# BIT_4.net
KiCad netlist of a schematic drawn in EasyEDA
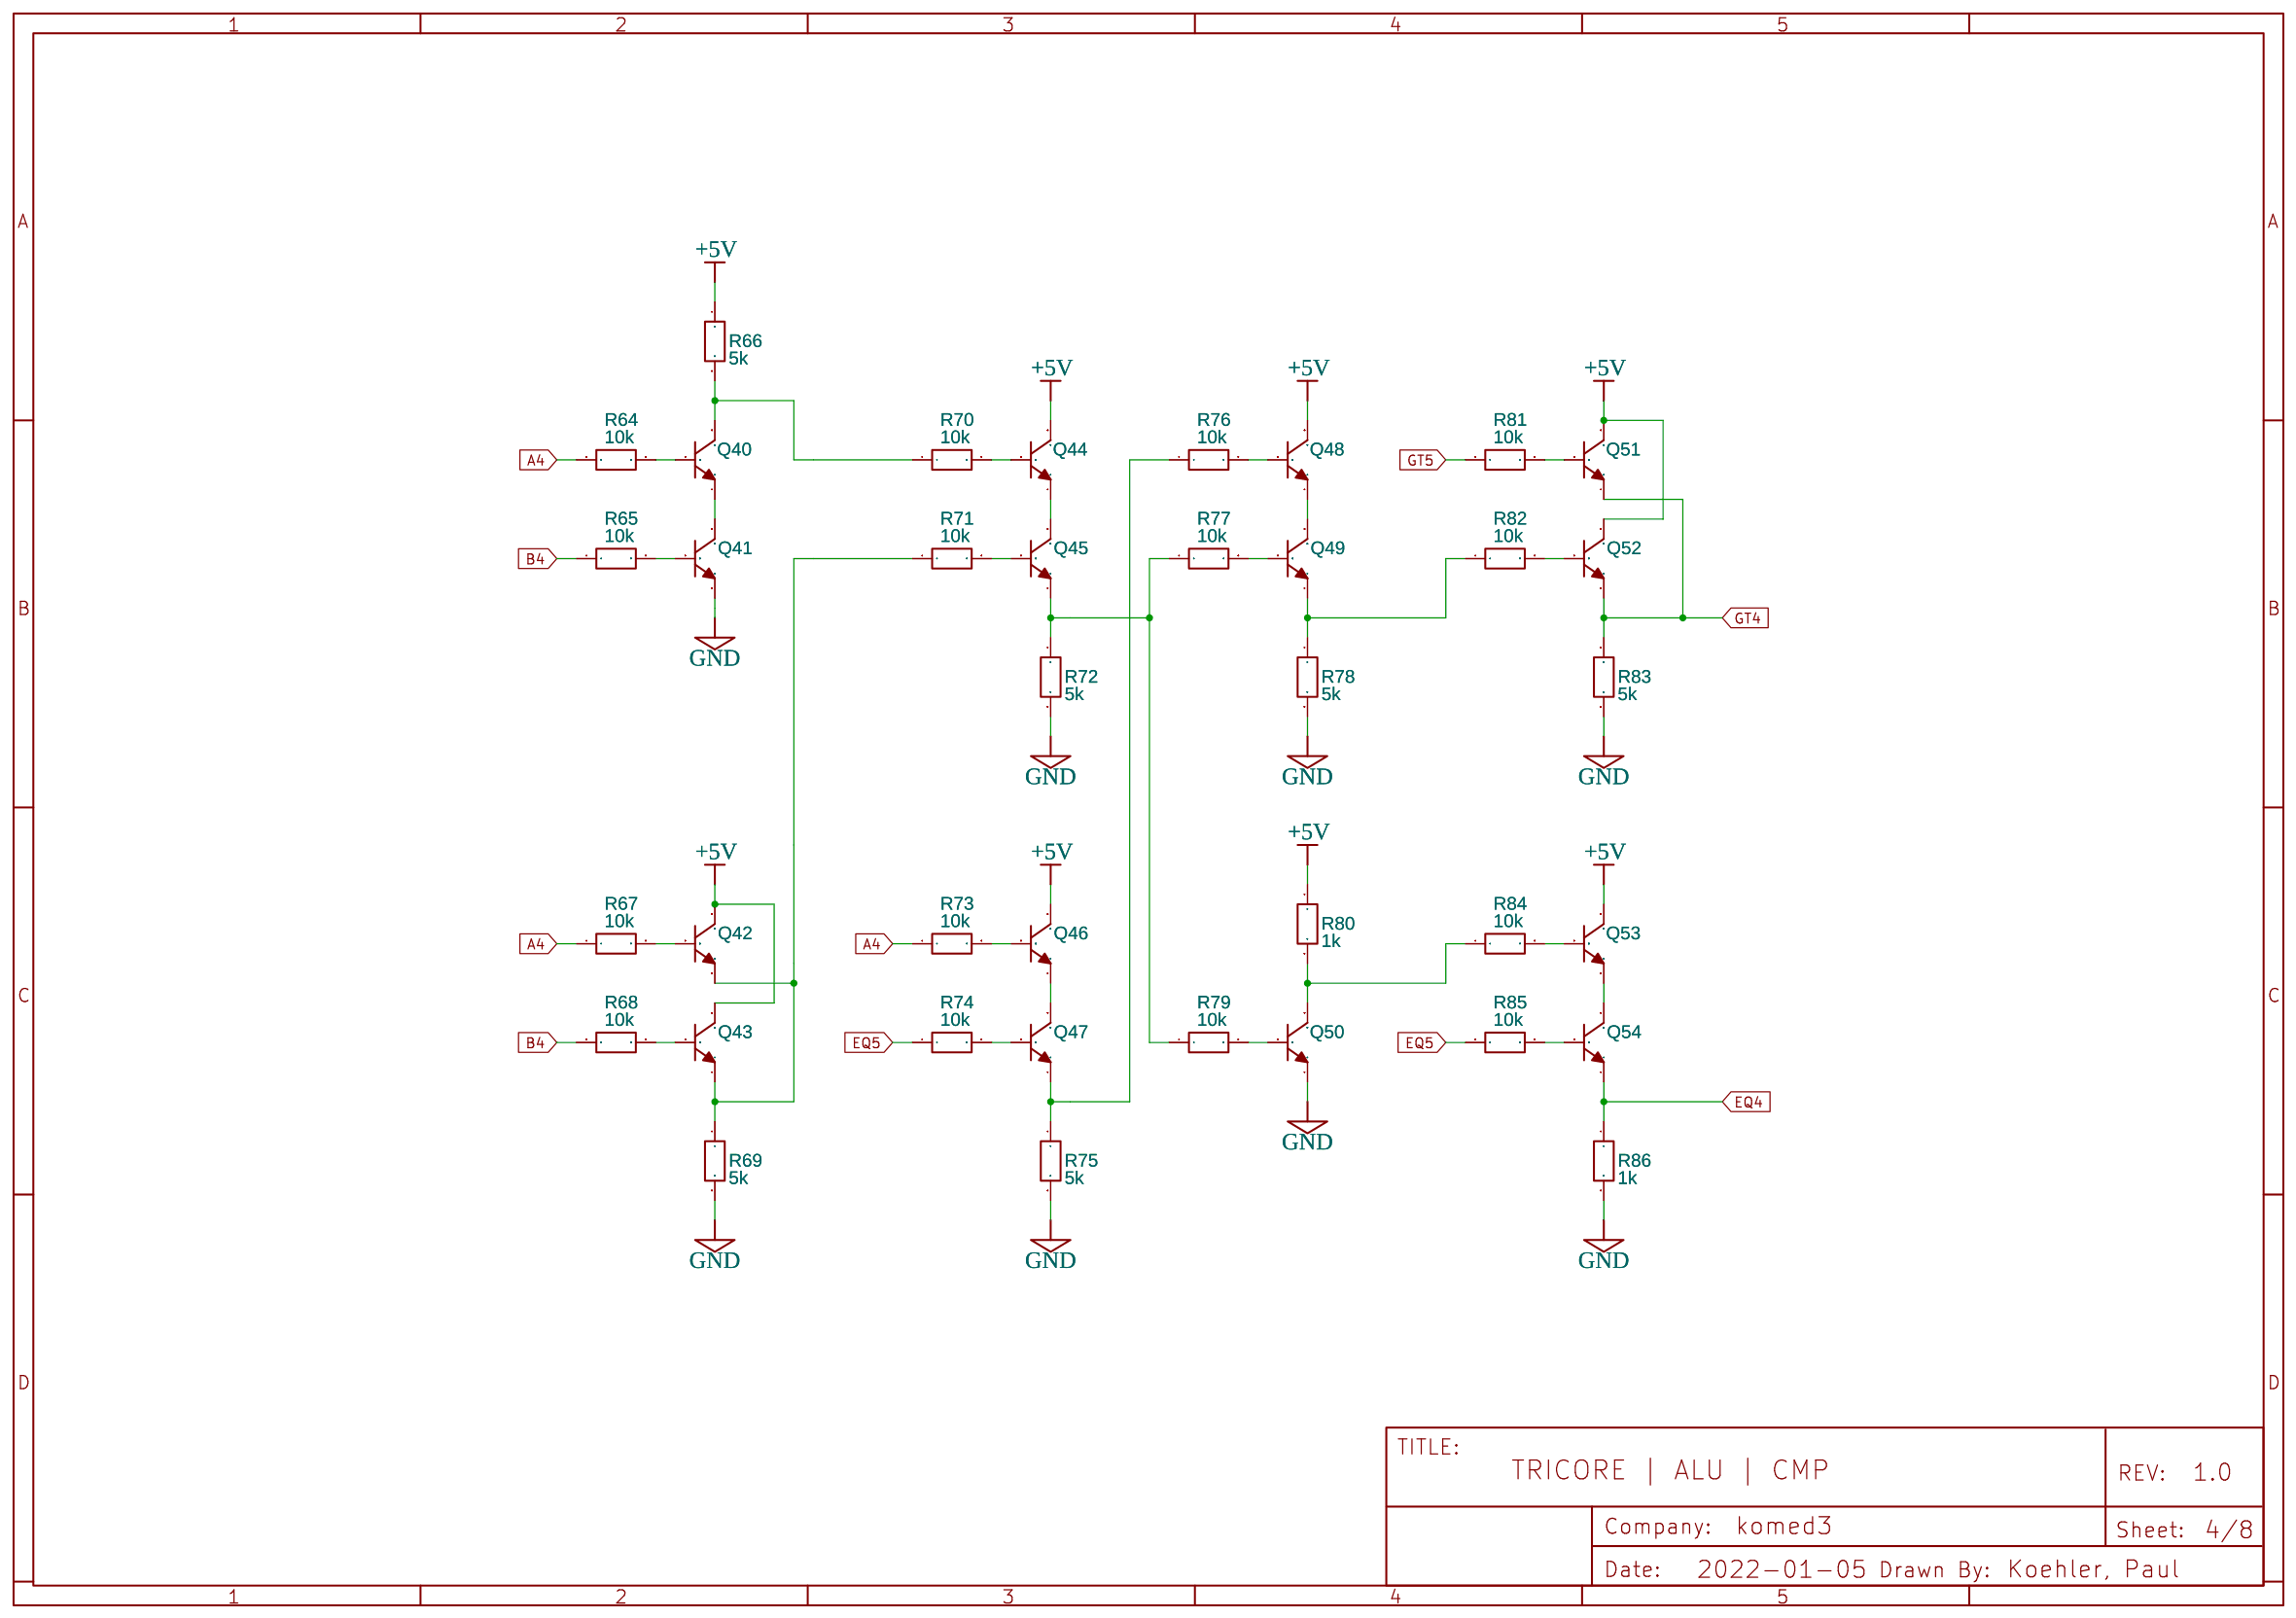
[diagram p0: schematic sheet]

(export (version "E")
  (design (tool "Eeschema 10.0.6"))
  (components
    (comp (ref "Q40")
      (value "2N3904(TO-92)")
      (fields (field (name "BOM_Manufacturer Part") "2N3904") (field (name "BOM_Supplier Part") "C118538"))
      (libsource (lib "") (part "2N3904(TO-92)"))
    )
    (comp (ref "Q41")
      (value "2N3904(TO-92)")
      (fields (field (name "BOM_Manufacturer Part") "2N3904") (field (name "BOM_Supplier Part") "C118538"))
      (libsource (lib "") (part "2N3904(TO-92)"))
    )
    (comp (ref "Q42")
      (value "2N3904(TO-92)")
      (fields (field (name "BOM_Manufacturer Part") "2N3904") (field (name "BOM_Supplier Part") "C118538"))
      (libsource (lib "") (part "2N3904(TO-92)"))
    )
    (comp (ref "Q43")
      (value "2N3904(TO-92)")
      (fields (field (name "BOM_Manufacturer Part") "2N3904") (field (name "BOM_Supplier Part") "C118538"))
      (libsource (lib "") (part "2N3904(TO-92)"))
    )
    (comp (ref "Q44")
      (value "2N3904(TO-92)")
      (fields (field (name "BOM_Manufacturer Part") "2N3904") (field (name "BOM_Supplier Part") "C118538"))
      (libsource (lib "") (part "2N3904(TO-92)"))
    )
    (comp (ref "Q45")
      (value "2N3904(TO-92)")
      (fields (field (name "BOM_Manufacturer Part") "2N3904") (field (name "BOM_Supplier Part") "C118538"))
      (libsource (lib "") (part "2N3904(TO-92)"))
    )
    (comp (ref "Q46")
      (value "2N3904(TO-92)")
      (fields (field (name "BOM_Manufacturer Part") "2N3904") (field (name "BOM_Supplier Part") "C118538"))
      (libsource (lib "") (part "2N3904(TO-92)"))
    )
    (comp (ref "Q47")
      (value "2N3904(TO-92)")
      (fields (field (name "BOM_Manufacturer Part") "2N3904") (field (name "BOM_Supplier Part") "C118538"))
      (libsource (lib "") (part "2N3904(TO-92)"))
    )
    (comp (ref "Q48")
      (value "2N3904(TO-92)")
      (fields (field (name "BOM_Manufacturer Part") "2N3904") (field (name "BOM_Supplier Part") "C118538"))
      (libsource (lib "") (part "2N3904(TO-92)"))
    )
    (comp (ref "Q49")
      (value "2N3904(TO-92)")
      (fields (field (name "BOM_Manufacturer Part") "2N3904") (field (name "BOM_Supplier Part") "C118538"))
      (libsource (lib "") (part "2N3904(TO-92)"))
    )
    (comp (ref "Q50")
      (value "2N3904(TO-92)")
      (fields (field (name "BOM_Manufacturer Part") "2N3904") (field (name "BOM_Supplier Part") "C118538"))
      (libsource (lib "") (part "2N3904(TO-92)"))
    )
    (comp (ref "Q51")
      (value "2N3904(TO-92)")
      (fields (field (name "BOM_Manufacturer Part") "2N3904") (field (name "BOM_Supplier Part") "C118538"))
      (libsource (lib "") (part "2N3904(TO-92)"))
    )
    (comp (ref "Q52")
      (value "2N3904(TO-92)")
      (fields (field (name "BOM_Manufacturer Part") "2N3904") (field (name "BOM_Supplier Part") "C118538"))
      (libsource (lib "") (part "2N3904(TO-92)"))
    )
    (comp (ref "Q53")
      (value "2N3904(TO-92)")
      (fields (field (name "BOM_Manufacturer Part") "2N3904") (field (name "BOM_Supplier Part") "C118538"))
      (libsource (lib "") (part "2N3904(TO-92)"))
    )
    (comp (ref "Q54")
      (value "2N3904(TO-92)")
      (fields (field (name "BOM_Manufacturer Part") "2N3904") (field (name "BOM_Supplier Part") "C118538"))
      (libsource (lib "") (part "2N3904(TO-92)"))
    )
    (comp (ref "R64") (value "10k") (libsource (lib "") (part "R_AXIAL-0.3_EU")))
    (comp (ref "R65") (value "10k") (libsource (lib "") (part "R_AXIAL-0.3_EU")))
    (comp (ref "R66") (value "5k") (libsource (lib "") (part "R_AXIAL-0.3_EU_1")))
    (comp (ref "R67") (value "10k") (libsource (lib "") (part "R_AXIAL-0.3_EU")))
    (comp (ref "R68") (value "10k") (libsource (lib "") (part "R_AXIAL-0.3_EU")))
    (comp (ref "R69") (value "5k") (libsource (lib "") (part "R_AXIAL-0.3_EU_1")))
    (comp (ref "R70") (value "10k") (libsource (lib "") (part "R_AXIAL-0.3_EU")))
    (comp (ref "R71") (value "10k") (libsource (lib "") (part "R_AXIAL-0.3_EU")))
    (comp (ref "R72") (value "5k") (libsource (lib "") (part "R_AXIAL-0.3_EU_1")))
    (comp (ref "R73") (value "10k") (libsource (lib "") (part "R_AXIAL-0.3_EU")))
    (comp (ref "R74") (value "10k") (libsource (lib "") (part "R_AXIAL-0.3_EU")))
    (comp (ref "R75") (value "5k") (libsource (lib "") (part "R_AXIAL-0.3_EU_1")))
    (comp (ref "R76") (value "10k") (libsource (lib "") (part "R_AXIAL-0.3_EU")))
    (comp (ref "R77") (value "10k") (libsource (lib "") (part "R_AXIAL-0.3_EU")))
    (comp (ref "R78") (value "5k") (libsource (lib "") (part "R_AXIAL-0.3_EU_1")))
    (comp (ref "R79") (value "10k") (libsource (lib "") (part "R_AXIAL-0.3_EU")))
    (comp (ref "R80") (value "1k") (libsource (lib "") (part "R_AXIAL-0.3_EU_1")))
    (comp (ref "R81") (value "10k") (libsource (lib "") (part "R_AXIAL-0.3_EU")))
    (comp (ref "R82") (value "10k") (libsource (lib "") (part "R_AXIAL-0.3_EU")))
    (comp (ref "R83") (value "5k") (libsource (lib "") (part "R_AXIAL-0.3_EU_1")))
    (comp (ref "R84") (value "10k") (libsource (lib "") (part "R_AXIAL-0.3_EU")))
    (comp (ref "R85") (value "10k") (libsource (lib "") (part "R_AXIAL-0.3_EU")))
    (comp (ref "R86") (value "1k") (libsource (lib "") (part "R_AXIAL-0.3_EU_1")))
  )
  (nets
    (net (code "1") (name "+5V") (class "Default")
      (node (ref "Q42") (pin "3") (pinfunction "C_3") (pintype "unspecified"))
      (node (ref "Q43") (pin "3") (pinfunction "C_3") (pintype "unspecified"))
      (node (ref "Q44") (pin "3") (pinfunction "C_3") (pintype "unspecified"))
      (node (ref "Q46") (pin "3") (pinfunction "C_3") (pintype "unspecified"))
      (node (ref "Q48") (pin "3") (pinfunction "C_3") (pintype "unspecified"))
      (node (ref "Q51") (pin "3") (pinfunction "C_3") (pintype "unspecified"))
      (node (ref "Q52") (pin "3") (pinfunction "C_3") (pintype "unspecified"))
      (node (ref "Q53") (pin "3") (pinfunction "C_3") (pintype "unspecified"))
      (node (ref "R66") (pin "1") (pinfunction "1_1") (pintype "unspecified"))
      (node (ref "R80") (pin "1") (pinfunction "1_1") (pintype "unspecified"))
    )
    (net (code "2") (name "A4") (class "Default")
      (node (ref "R64") (pin "1") (pinfunction "1_1") (pintype "unspecified"))
      (node (ref "R67") (pin "1") (pinfunction "1_1") (pintype "unspecified"))
      (node (ref "R73") (pin "1") (pinfunction "1_1") (pintype "unspecified"))
    )
    (net (code "3") (name "B4") (class "Default")
      (node (ref "R65") (pin "1") (pinfunction "1_1") (pintype "unspecified"))
      (node (ref "R68") (pin "1") (pinfunction "1_1") (pintype "unspecified"))
    )
    (net (code "4") (name "EQ4") (class "Default")
      (node (ref "Q54") (pin "1") (pinfunction "E_1") (pintype "unspecified"))
      (node (ref "R86") (pin "1") (pinfunction "1_1") (pintype "unspecified"))
    )
    (net (code "5") (name "EQ5") (class "Default")
      (node (ref "R74") (pin "1") (pinfunction "1_1") (pintype "unspecified"))
      (node (ref "R85") (pin "1") (pinfunction "1_1") (pintype "unspecified"))
    )
    (net (code "6") (name "GND") (class "Default")
      (node (ref "Q41") (pin "1") (pinfunction "E_1") (pintype "unspecified"))
      (node (ref "Q50") (pin "1") (pinfunction "E_1") (pintype "unspecified"))
      (node (ref "R69") (pin "2") (pinfunction "2_2") (pintype "unspecified"))
      (node (ref "R72") (pin "2") (pinfunction "2_2") (pintype "unspecified"))
      (node (ref "R75") (pin "2") (pinfunction "2_2") (pintype "unspecified"))
      (node (ref "R78") (pin "2") (pinfunction "2_2") (pintype "unspecified"))
      (node (ref "R83") (pin "2") (pinfunction "2_2") (pintype "unspecified"))
      (node (ref "R86") (pin "2") (pinfunction "2_2") (pintype "unspecified"))
    )
    (net (code "7") (name "GT4") (class "Default")
      (node (ref "Q51") (pin "1") (pinfunction "E_1") (pintype "unspecified"))
      (node (ref "Q52") (pin "1") (pinfunction "E_1") (pintype "unspecified"))
      (node (ref "R83") (pin "1") (pinfunction "1_1") (pintype "unspecified"))
    )
    (net (code "8") (name "GT5") (class "Default")
      (node (ref "R81") (pin "1") (pinfunction "1_1") (pintype "unspecified"))
    )
    (net (code "9") (name "Net-(Q40-B)") (class "Default")
      (node (ref "Q40") (pin "2") (pinfunction "B_2") (pintype "unspecified"))
      (node (ref "R64") (pin "2") (pinfunction "2_2") (pintype "unspecified"))
    )
    (net (code "10") (name "Net-(Q40-C)") (class "Default")
      (node (ref "Q40") (pin "3") (pinfunction "C_3") (pintype "unspecified"))
      (node (ref "R66") (pin "2") (pinfunction "2_2") (pintype "unspecified"))
      (node (ref "R70") (pin "1") (pinfunction "1_1") (pintype "unspecified"))
    )
    (net (code "11") (name "Net-(Q40-E)") (class "Default")
      (node (ref "Q40") (pin "1") (pinfunction "E_1") (pintype "unspecified"))
      (node (ref "Q41") (pin "3") (pinfunction "C_3") (pintype "unspecified"))
    )
    (net (code "12") (name "Net-(Q41-B)") (class "Default")
      (node (ref "Q41") (pin "2") (pinfunction "B_2") (pintype "unspecified"))
      (node (ref "R65") (pin "2") (pinfunction "2_2") (pintype "unspecified"))
    )
    (net (code "13") (name "Net-(Q42-B)") (class "Default")
      (node (ref "Q42") (pin "2") (pinfunction "B_2") (pintype "unspecified"))
      (node (ref "R67") (pin "2") (pinfunction "2_2") (pintype "unspecified"))
    )
    (net (code "14") (name "Net-(Q42-E)") (class "Default")
      (node (ref "Q42") (pin "1") (pinfunction "E_1") (pintype "unspecified"))
      (node (ref "Q43") (pin "1") (pinfunction "E_1") (pintype "unspecified"))
      (node (ref "R69") (pin "1") (pinfunction "1_1") (pintype "unspecified"))
      (node (ref "R71") (pin "1") (pinfunction "1_1") (pintype "unspecified"))
    )
    (net (code "15") (name "Net-(Q43-B)") (class "Default")
      (node (ref "Q43") (pin "2") (pinfunction "B_2") (pintype "unspecified"))
      (node (ref "R68") (pin "2") (pinfunction "2_2") (pintype "unspecified"))
    )
    (net (code "16") (name "Net-(Q44-B)") (class "Default")
      (node (ref "Q44") (pin "2") (pinfunction "B_2") (pintype "unspecified"))
      (node (ref "R70") (pin "2") (pinfunction "2_2") (pintype "unspecified"))
    )
    (net (code "17") (name "Net-(Q44-E)") (class "Default")
      (node (ref "Q44") (pin "1") (pinfunction "E_1") (pintype "unspecified"))
      (node (ref "Q45") (pin "3") (pinfunction "C_3") (pintype "unspecified"))
    )
    (net (code "18") (name "Net-(Q45-B)") (class "Default")
      (node (ref "Q45") (pin "2") (pinfunction "B_2") (pintype "unspecified"))
      (node (ref "R71") (pin "2") (pinfunction "2_2") (pintype "unspecified"))
    )
    (net (code "19") (name "Net-(Q45-E)") (class "Default")
      (node (ref "Q45") (pin "1") (pinfunction "E_1") (pintype "unspecified"))
      (node (ref "R72") (pin "1") (pinfunction "1_1") (pintype "unspecified"))
      (node (ref "R77") (pin "1") (pinfunction "1_1") (pintype "unspecified"))
      (node (ref "R79") (pin "1") (pinfunction "1_1") (pintype "unspecified"))
    )
    (net (code "20") (name "Net-(Q46-B)") (class "Default")
      (node (ref "Q46") (pin "2") (pinfunction "B_2") (pintype "unspecified"))
      (node (ref "R73") (pin "2") (pinfunction "2_2") (pintype "unspecified"))
    )
    (net (code "21") (name "Net-(Q46-E)") (class "Default")
      (node (ref "Q46") (pin "1") (pinfunction "E_1") (pintype "unspecified"))
      (node (ref "Q47") (pin "3") (pinfunction "C_3") (pintype "unspecified"))
    )
    (net (code "22") (name "Net-(Q47-B)") (class "Default")
      (node (ref "Q47") (pin "2") (pinfunction "B_2") (pintype "unspecified"))
      (node (ref "R74") (pin "2") (pinfunction "2_2") (pintype "unspecified"))
    )
    (net (code "23") (name "Net-(Q47-E)") (class "Default")
      (node (ref "Q47") (pin "1") (pinfunction "E_1") (pintype "unspecified"))
      (node (ref "R75") (pin "1") (pinfunction "1_1") (pintype "unspecified"))
      (node (ref "R76") (pin "1") (pinfunction "1_1") (pintype "unspecified"))
    )
    (net (code "24") (name "Net-(Q48-B)") (class "Default")
      (node (ref "Q48") (pin "2") (pinfunction "B_2") (pintype "unspecified"))
      (node (ref "R76") (pin "2") (pinfunction "2_2") (pintype "unspecified"))
    )
    (net (code "25") (name "Net-(Q48-E)") (class "Default")
      (node (ref "Q48") (pin "1") (pinfunction "E_1") (pintype "unspecified"))
      (node (ref "Q49") (pin "3") (pinfunction "C_3") (pintype "unspecified"))
    )
    (net (code "26") (name "Net-(Q49-B)") (class "Default")
      (node (ref "Q49") (pin "2") (pinfunction "B_2") (pintype "unspecified"))
      (node (ref "R77") (pin "2") (pinfunction "2_2") (pintype "unspecified"))
    )
    (net (code "27") (name "Net-(Q49-E)") (class "Default")
      (node (ref "Q49") (pin "1") (pinfunction "E_1") (pintype "unspecified"))
      (node (ref "R78") (pin "1") (pinfunction "1_1") (pintype "unspecified"))
      (node (ref "R82") (pin "1") (pinfunction "1_1") (pintype "unspecified"))
    )
    (net (code "28") (name "Net-(Q50-B)") (class "Default")
      (node (ref "Q50") (pin "2") (pinfunction "B_2") (pintype "unspecified"))
      (node (ref "R79") (pin "2") (pinfunction "2_2") (pintype "unspecified"))
    )
    (net (code "29") (name "Net-(Q50-C)") (class "Default")
      (node (ref "Q50") (pin "3") (pinfunction "C_3") (pintype "unspecified"))
      (node (ref "R80") (pin "2") (pinfunction "2_2") (pintype "unspecified"))
      (node (ref "R84") (pin "1") (pinfunction "1_1") (pintype "unspecified"))
    )
    (net (code "30") (name "Net-(Q51-B)") (class "Default")
      (node (ref "Q51") (pin "2") (pinfunction "B_2") (pintype "unspecified"))
      (node (ref "R81") (pin "2") (pinfunction "2_2") (pintype "unspecified"))
    )
    (net (code "31") (name "Net-(Q52-B)") (class "Default")
      (node (ref "Q52") (pin "2") (pinfunction "B_2") (pintype "unspecified"))
      (node (ref "R82") (pin "2") (pinfunction "2_2") (pintype "unspecified"))
    )
    (net (code "32") (name "Net-(Q53-B)") (class "Default")
      (node (ref "Q53") (pin "2") (pinfunction "B_2") (pintype "unspecified"))
      (node (ref "R84") (pin "2") (pinfunction "2_2") (pintype "unspecified"))
    )
    (net (code "33") (name "Net-(Q53-E)") (class "Default")
      (node (ref "Q53") (pin "1") (pinfunction "E_1") (pintype "unspecified"))
      (node (ref "Q54") (pin "3") (pinfunction "C_3") (pintype "unspecified"))
    )
    (net (code "34") (name "Net-(Q54-B)") (class "Default")
      (node (ref "Q54") (pin "2") (pinfunction "B_2") (pintype "unspecified"))
      (node (ref "R85") (pin "2") (pinfunction "2_2") (pintype "unspecified"))
    )
  )
)
